# XtendTeensy.net
KiCad netlist of a schematic drawn in EAGLE
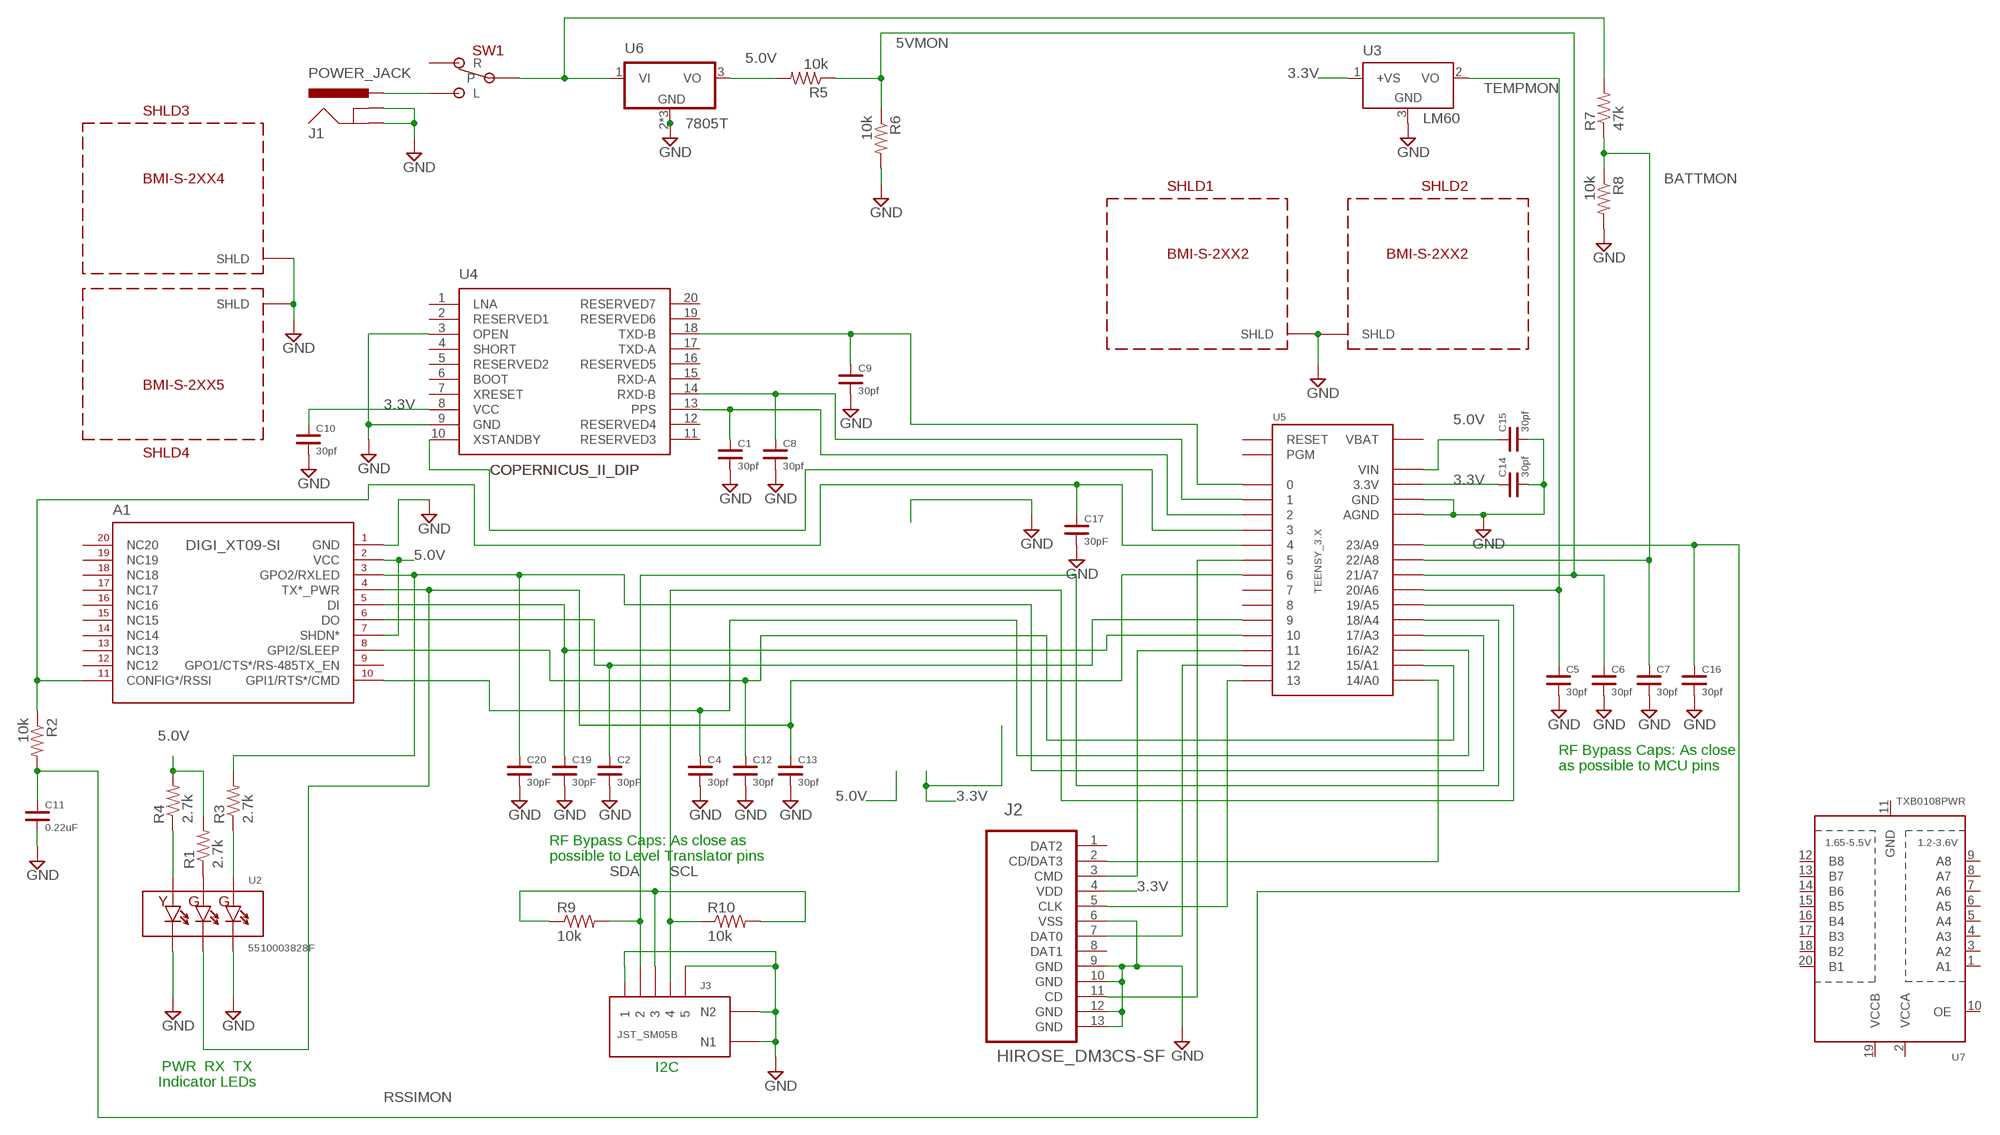
[diagram p0: schematic, sheet 1]

(export (version "E")
  (design (tool "Eeschema 10.0.6"))
  (components
    (comp (ref "A1")
      (value "DIGI_XT09-SI")
      (footprint "eagle-import:DIGI_XT09-SI")
      (libsource (lib "eagle-import") (part "DIGI_XT09-SI"))
    )
    (comp (ref "C1")
      (value "30pf")
      (footprint "eagle-import:C0603")
      (libsource (lib "eagle-import") (part "C-USC0603"))
    )
    (comp (ref "C2")
      (value "30pF")
      (footprint "eagle-import:C0603")
      (libsource (lib "eagle-import") (part "C-USC0603"))
    )
    (comp (ref "C4")
      (value "30pf")
      (footprint "eagle-import:C0603")
      (libsource (lib "eagle-import") (part "C-USC0603"))
    )
    (comp (ref "C5")
      (value "30pf")
      (footprint "eagle-import:C0603")
      (libsource (lib "eagle-import") (part "C-USC0603"))
    )
    (comp (ref "C6")
      (value "30pf")
      (footprint "eagle-import:C0603")
      (libsource (lib "eagle-import") (part "C-USC0603"))
    )
    (comp (ref "C7")
      (value "30pf")
      (footprint "eagle-import:C0603")
      (libsource (lib "eagle-import") (part "C-USC0603"))
    )
    (comp (ref "C8")
      (value "30pf")
      (footprint "eagle-import:C0603")
      (libsource (lib "eagle-import") (part "C-USC0603"))
    )
    (comp (ref "C9")
      (value "30pf")
      (footprint "eagle-import:C0603")
      (libsource (lib "eagle-import") (part "C-USC0603"))
    )
    (comp (ref "C10")
      (value "30pf")
      (footprint "eagle-import:C0603")
      (libsource (lib "eagle-import") (part "C-USC0603"))
    )
    (comp (ref "C11")
      (value "0.22uF")
      (footprint "eagle-import:C0603")
      (libsource (lib "eagle-import") (part "C-USC0603"))
    )
    (comp (ref "C12")
      (value "30pf")
      (footprint "eagle-import:C0603")
      (libsource (lib "eagle-import") (part "C-USC0603"))
    )
    (comp (ref "C13")
      (value "30pf")
      (footprint "eagle-import:C0603")
      (libsource (lib "eagle-import") (part "C-USC0603"))
    )
    (comp (ref "C14")
      (value "30pf")
      (footprint "eagle-import:C0603")
      (libsource (lib "eagle-import") (part "C-USC0603"))
    )
    (comp (ref "C15")
      (value "30pf")
      (footprint "eagle-import:C0603")
      (libsource (lib "eagle-import") (part "C-USC0603"))
    )
    (comp (ref "C16")
      (value "30pf")
      (footprint "eagle-import:C0603")
      (libsource (lib "eagle-import") (part "C-USC0603"))
    )
    (comp (ref "C17")
      (value "30pF")
      (footprint "eagle-import:C0603")
      (libsource (lib "eagle-import") (part "C-USC0603"))
    )
    (comp (ref "C19")
      (value "30pF")
      (footprint "eagle-import:C0603")
      (libsource (lib "eagle-import") (part "C-USC0603"))
    )
    (comp (ref "C20")
      (value "30pF")
      (footprint "eagle-import:C0603")
      (libsource (lib "eagle-import") (part "C-USC0603"))
    )
    (comp (ref "J1")
      (value "POWER_JACK")
      (footprint "eagle-import:PWR_JACK_BB")
      (libsource (lib "eagle-import") (part "POWER_JACK"))
    )
    (comp (ref "J2")
      (value "HIROSE_DM3CS-SF")
      (footprint "eagle-import:HIROSE_DM3CS-SF")
      (fields (field (name "MPN") "DM3CS-SF"))
      (libsource (lib "eagle-import") (part "HIROSE_DM3CS-SF"))
    )
    (comp (ref "J3")
      (value "JST_SM05B")
      (footprint "eagle-import:JST_SM05B")
      (libsource (lib "eagle-import") (part "JST_SM05B"))
    )
    (comp (ref "R1")
      (value "2.7k")
      (footprint "eagle-import:R0805")
      (libsource (lib "eagle-import") (part "R-US_R0805"))
    )
    (comp (ref "R2")
      (value "10k")
      (footprint "eagle-import:R0805")
      (libsource (lib "eagle-import") (part "R-US_R0805"))
    )
    (comp (ref "R3")
      (value "2.7k")
      (footprint "eagle-import:R0805")
      (libsource (lib "eagle-import") (part "R-US_R0805"))
    )
    (comp (ref "R4")
      (value "2.7k")
      (footprint "eagle-import:R0805")
      (libsource (lib "eagle-import") (part "R-US_R0805"))
    )
    (comp (ref "R5")
      (value "10k")
      (footprint "eagle-import:R0805")
      (libsource (lib "eagle-import") (part "R-US_R0805"))
    )
    (comp (ref "R6")
      (value "10k")
      (footprint "eagle-import:R0805")
      (libsource (lib "eagle-import") (part "R-US_R0805"))
    )
    (comp (ref "R7")
      (value "47k")
      (footprint "eagle-import:R0805")
      (libsource (lib "eagle-import") (part "R-US_R0805"))
    )
    (comp (ref "R8")
      (value "10k")
      (footprint "eagle-import:R0805")
      (libsource (lib "eagle-import") (part "R-US_R0805"))
    )
    (comp (ref "R9")
      (value "10k")
      (footprint "eagle-import:R0805")
      (libsource (lib "eagle-import") (part "R-US_R0805"))
    )
    (comp (ref "R10")
      (value "10k")
      (footprint "eagle-import:R0805")
      (libsource (lib "eagle-import") (part "R-US_R0805"))
    )
    (comp (ref "SHLD1")
      (value "BMI-S-2XX2")
      (footprint "eagle-import:BMI-S-207-F")
      (libsource (lib "eagle-import") (part "BMI-S-2XX2"))
    )
    (comp (ref "SHLD2")
      (value "BMI-S-2XX2")
      (footprint "eagle-import:BMI-S-207-F")
      (libsource (lib "eagle-import") (part "BMI-S-2XX2"))
    )
    (comp (ref "SHLD3")
      (value "BMI-S-2XX4")
      (footprint "eagle-import:BMI-S-206-F_COPERNICUS")
      (libsource (lib "eagle-import") (part "BMI-S-2XX4"))
    )
    (comp (ref "SHLD4")
      (value "BMI-S-2XX5")
      (footprint "eagle-import:BMI-S-206-F_COPERNICUS_M")
      (libsource (lib "eagle-import") (part "BMI-S-2XX5"))
    )
    (comp (ref "SW1")
      (value "SPDT_RA_3A")
      (footprint "eagle-import:ESWITCH_SPDT_RA")
      (libsource (lib "eagle-import") (part "SPDT_RA_3A"))
    )
    (comp (ref "U2")
      (value "5510003828F")
      (footprint "eagle-import:TRIPLE_LED_SIDE_0.1IN")
      (libsource (lib "eagle-import") (part "5510003828F"))
    )
    (comp (ref "U3")
      (value "LM60")
      (footprint "eagle-import:TO92")
      (libsource (lib "eagle-import") (part "LM60"))
    )
    (comp (ref "U4")
      (value "COPERNICUS_II_DIP")
      (footprint "eagle-import:COPERNICUS_II_DIP")
      (libsource (lib "eagle-import") (part "COPERNICUS_II_DIP"))
    )
    (comp (ref "U5")
      (value "TEENSY_3.X")
      (footprint "eagle-import:TEENSY_3.X_PERIPHERY")
      (libsource (lib "eagle-import") (part "TEENSY_3.X"))
    )
    (comp (ref "U6")
      (value "7805T")
      (footprint "eagle-import:TO220H")
      (libsource (lib "eagle-import") (part "78T05"))
    )
    (comp (ref "U7")
      (value "TXB0108PWR")
      (footprint "eagle-import:TSSOP20")
      (libsource (lib "eagle-import") (part "TXB0108PWR"))
    )
  )
  (nets
    (net (code "1") (name "/3.3V") (class "Default")
      (node (ref "C10") (pin "1") (pinfunction "1_1") (pintype "passive"))
      (node (ref "C14") (pin "1") (pinfunction "1_1") (pintype "passive"))
      (node (ref "J2") (pin "4") (pinfunction "VDD_4") (pintype "passive"))
      (node (ref "U3") (pin "1") (pinfunction "+VS_1") (pintype "input"))
      (node (ref "U4") (pin "8") (pinfunction "VCC_8") (pintype "bidirectional"))
      (node (ref "U5") (pin "3.3V") (pinfunction "3.3V_3.3V") (pintype "power_in"))
      (node (ref "U5") (pin "3.3V1") (pinfunction "3.3V_3.3V1") (pintype "power_in"))
    )
    (net (code "2") (name "/5.0V") (class "Default")
      (node (ref "A1") (pin "P$2") (pinfunction "VCC_P$2") (pintype "power_in"))
      (node (ref "A1") (pin "P$7") (pinfunction "SHDN*_P$7") (pintype "input"))
      (node (ref "C15") (pin "1") (pinfunction "1_1") (pintype "passive"))
      (node (ref "R1") (pin "2") (pinfunction "2_2") (pintype "passive"))
      (node (ref "R4") (pin "2") (pinfunction "2_2") (pintype "passive"))
      (node (ref "R5") (pin "2") (pinfunction "2_2") (pintype "passive"))
      (node (ref "U5") (pin "VIN") (pinfunction "VIN_VIN") (pintype "input"))
      (node (ref "U6") (pin "3") (pinfunction "VO_3") (pintype "passive"))
    )
    (net (code "3") (name "/5VMON") (class "Default")
      (node (ref "C6") (pin "1") (pinfunction "1_1") (pintype "passive"))
      (node (ref "R5") (pin "1") (pinfunction "1_1") (pintype "passive"))
      (node (ref "R6") (pin "1") (pinfunction "1_1") (pintype "passive"))
      (node (ref "U5") (pin "21/A7") (pinfunction "21/A7_21/A7") (pintype "bidirectional"))
    )
    (net (code "4") (name "/BATTMON") (class "Default")
      (node (ref "C7") (pin "1") (pinfunction "1_1") (pintype "passive"))
      (node (ref "R7") (pin "1") (pinfunction "1_1") (pintype "passive"))
      (node (ref "R8") (pin "1") (pinfunction "1_1") (pintype "passive"))
      (node (ref "U5") (pin "22/A8") (pinfunction "22/A8_22/A8") (pintype "bidirectional"))
    )
    (net (code "5") (name "/RSSIMON") (class "Default")
      (node (ref "C11") (pin "1") (pinfunction "1_1") (pintype "passive"))
      (node (ref "C16") (pin "1") (pinfunction "1_1") (pintype "passive"))
      (node (ref "R2") (pin "2") (pinfunction "2_2") (pintype "passive"))
      (node (ref "U5") (pin "23/A9") (pinfunction "23/A9_23/A9") (pintype "bidirectional"))
    )
    (net (code "6") (name "/SCL") (class "Default")
      (node (ref "J3") (pin "P$4") (pinfunction "4_P$4") (pintype "bidirectional"))
      (node (ref "R10") (pin "1") (pinfunction "1_1") (pintype "passive"))
      (node (ref "U5") (pin "19/A5") (pinfunction "19/A5_19/A5") (pintype "bidirectional"))
    )
    (net (code "7") (name "/SDA") (class "Default")
      (node (ref "J3") (pin "P$2") (pinfunction "2_P$2") (pintype "bidirectional"))
      (node (ref "R9") (pin "2") (pinfunction "2_2") (pintype "passive"))
      (node (ref "U5") (pin "18/A4") (pinfunction "18/A4_18/A4") (pintype "bidirectional"))
    )
    (net (code "8") (name "/TEMPMON") (class "Default")
      (node (ref "C5") (pin "1") (pinfunction "1_1") (pintype "passive"))
      (node (ref "U3") (pin "2") (pinfunction "VO_2") (pintype "input"))
      (node (ref "U5") (pin "20/A6") (pinfunction "20/A6_20/A6") (pintype "bidirectional"))
    )
    (net (code "9") (name "GND") (class "Default")
      (node (ref "A1") (pin "P$1") (pinfunction "GND_P$1") (pintype "power_in"))
      (node (ref "A1") (pin "P$21") (pinfunction "GND_P$21") (pintype "power_in"))
      (node (ref "A1") (pin "P$22") (pinfunction "GND_P$22") (pintype "power_in"))
      (node (ref "A1") (pin "P$23") (pinfunction "GND_P$23") (pintype "power_in"))
      (node (ref "A1") (pin "P$24") (pinfunction "GND_P$24") (pintype "power_in"))
      (node (ref "C1") (pin "2") (pinfunction "2_2") (pintype "passive"))
      (node (ref "C10") (pin "2") (pinfunction "2_2") (pintype "passive"))
      (node (ref "C11") (pin "2") (pinfunction "2_2") (pintype "passive"))
      (node (ref "C12") (pin "2") (pinfunction "2_2") (pintype "passive"))
      (node (ref "C13") (pin "2") (pinfunction "2_2") (pintype "passive"))
      (node (ref "C14") (pin "2") (pinfunction "2_2") (pintype "passive"))
      (node (ref "C15") (pin "2") (pinfunction "2_2") (pintype "passive"))
      (node (ref "C16") (pin "2") (pinfunction "2_2") (pintype "passive"))
      (node (ref "C17") (pin "2") (pinfunction "2_2") (pintype "passive"))
      (node (ref "C19") (pin "2") (pinfunction "2_2") (pintype "passive"))
      (node (ref "C2") (pin "2") (pinfunction "2_2") (pintype "passive"))
      (node (ref "C20") (pin "2") (pinfunction "2_2") (pintype "passive"))
      (node (ref "C4") (pin "2") (pinfunction "2_2") (pintype "passive"))
      (node (ref "C5") (pin "2") (pinfunction "2_2") (pintype "passive"))
      (node (ref "C6") (pin "2") (pinfunction "2_2") (pintype "passive"))
      (node (ref "C7") (pin "2") (pinfunction "2_2") (pintype "passive"))
      (node (ref "C8") (pin "2") (pinfunction "2_2") (pintype "passive"))
      (node (ref "C9") (pin "2") (pinfunction "2_2") (pintype "passive"))
      (node (ref "J1") (pin "GND") (pinfunction "GND_GND") (pintype "bidirectional"))
      (node (ref "J1") (pin "GNDBREAK") (pinfunction "GNDBREAK_GNDBREAK") (pintype "bidirectional"))
      (node (ref "J2") (pin "10") (pinfunction "GND_10") (pintype "passive"))
      (node (ref "J2") (pin "12") (pinfunction "GND_12") (pintype "passive"))
      (node (ref "J2") (pin "13") (pinfunction "GND_13") (pintype "passive"))
      (node (ref "J2") (pin "6") (pinfunction "VSS_6") (pintype "passive"))
      (node (ref "J2") (pin "9") (pinfunction "GND_9") (pintype "passive"))
      (node (ref "J3") (pin "P$1") (pinfunction "1_P$1") (pintype "bidirectional"))
      (node (ref "J3") (pin "P$5") (pinfunction "5_P$5") (pintype "bidirectional"))
      (node (ref "J3") (pin "P$6") (pinfunction "N1_P$6") (pintype "bidirectional"))
      (node (ref "J3") (pin "P$7") (pinfunction "N2_P$7") (pintype "bidirectional"))
      (node (ref "R6") (pin "2") (pinfunction "2_2") (pintype "passive"))
      (node (ref "R8") (pin "2") (pinfunction "2_2") (pintype "passive"))
      (node (ref "SHLD1") (pin "P$10") (pinfunction "SHLD_P$10") (pintype "bidirectional"))
      (node (ref "SHLD1") (pin "P$11") (pinfunction "SHLD_P$11") (pintype "bidirectional"))
      (node (ref "SHLD1") (pin "P$12") (pinfunction "SHLD_P$12") (pintype "bidirectional"))
      (node (ref "SHLD1") (pin "P$14") (pinfunction "SHLD_P$14") (pintype "bidirectional"))
      (node (ref "SHLD1") (pin "P$15") (pinfunction "SHLD_P$15") (pintype "bidirectional"))
      (node (ref "SHLD1") (pin "P$16") (pinfunction "SHLD_P$16") (pintype "bidirectional"))
      (node (ref "SHLD1") (pin "P$17") (pinfunction "SHLD_P$17") (pintype "bidirectional"))
      (node (ref "SHLD1") (pin "P$18") (pinfunction "SHLD_P$18") (pintype "bidirectional"))
      (node (ref "SHLD1") (pin "P$19") (pinfunction "SHLD_P$19") (pintype "bidirectional"))
      (node (ref "SHLD1") (pin "P$2") (pinfunction "SHLD_P$2") (pintype "bidirectional"))
      (node (ref "SHLD1") (pin "P$20") (pinfunction "SHLD_P$20") (pintype "bidirectional"))
      (node (ref "SHLD1") (pin "P$21") (pinfunction "SHLD_P$21") (pintype "bidirectional"))
      (node (ref "SHLD1") (pin "P$22") (pinfunction "SHLD_P$22") (pintype "bidirectional"))
      (node (ref "SHLD1") (pin "P$23") (pinfunction "SHLD_P$23") (pintype "bidirectional"))
      (node (ref "SHLD1") (pin "P$24") (pinfunction "SHLD_P$24") (pintype "bidirectional"))
      (node (ref "SHLD1") (pin "P$25") (pinfunction "SHLD_P$25") (pintype "bidirectional"))
      (node (ref "SHLD1") (pin "P$26") (pinfunction "SHLD_P$26") (pintype "bidirectional"))
      (node (ref "SHLD1") (pin "P$27") (pinfunction "SHLD_P$27") (pintype "bidirectional"))
      (node (ref "SHLD1") (pin "P$28") (pinfunction "SHLD_P$28") (pintype "bidirectional"))
      (node (ref "SHLD1") (pin "P$29") (pinfunction "SHLD_P$29") (pintype "bidirectional"))
      (node (ref "SHLD1") (pin "P$3") (pinfunction "SHLD_P$3") (pintype "bidirectional"))
      (node (ref "SHLD1") (pin "P$30") (pinfunction "SHLD_P$30") (pintype "bidirectional"))
      (node (ref "SHLD1") (pin "P$31") (pinfunction "SHLD_P$31") (pintype "bidirectional"))
      (node (ref "SHLD1") (pin "P$32") (pinfunction "SHLD_P$32") (pintype "bidirectional"))
      (node (ref "SHLD1") (pin "P$33") (pinfunction "SHLD_P$33") (pintype "bidirectional"))
      (node (ref "SHLD1") (pin "P$34") (pinfunction "SHLD_P$34") (pintype "bidirectional"))
      (node (ref "SHLD1") (pin "P$4") (pinfunction "SHLD_P$4") (pintype "bidirectional"))
      (node (ref "SHLD1") (pin "P$5") (pinfunction "SHLD_P$5") (pintype "bidirectional"))
      (node (ref "SHLD1") (pin "P$6") (pinfunction "SHLD_P$6") (pintype "bidirectional"))
      (node (ref "SHLD1") (pin "P$7") (pinfunction "SHLD_P$7") (pintype "bidirectional"))
      (node (ref "SHLD1") (pin "P$8") (pinfunction "SHLD_P$8") (pintype "bidirectional"))
      (node (ref "SHLD1") (pin "P$9") (pinfunction "SHLD_P$9") (pintype "bidirectional"))
      (node (ref "SHLD2") (pin "P$10") (pinfunction "SHLD_P$10") (pintype "bidirectional"))
      (node (ref "SHLD2") (pin "P$11") (pinfunction "SHLD_P$11") (pintype "bidirectional"))
      (node (ref "SHLD2") (pin "P$12") (pinfunction "SHLD_P$12") (pintype "bidirectional"))
      (node (ref "SHLD2") (pin "P$14") (pinfunction "SHLD_P$14") (pintype "bidirectional"))
      (node (ref "SHLD2") (pin "P$15") (pinfunction "SHLD_P$15") (pintype "bidirectional"))
      (node (ref "SHLD2") (pin "P$16") (pinfunction "SHLD_P$16") (pintype "bidirectional"))
      (node (ref "SHLD2") (pin "P$17") (pinfunction "SHLD_P$17") (pintype "bidirectional"))
      (node (ref "SHLD2") (pin "P$18") (pinfunction "SHLD_P$18") (pintype "bidirectional"))
      (node (ref "SHLD2") (pin "P$19") (pinfunction "SHLD_P$19") (pintype "bidirectional"))
      (node (ref "SHLD2") (pin "P$2") (pinfunction "SHLD_P$2") (pintype "bidirectional"))
      (node (ref "SHLD2") (pin "P$20") (pinfunction "SHLD_P$20") (pintype "bidirectional"))
      (node (ref "SHLD2") (pin "P$21") (pinfunction "SHLD_P$21") (pintype "bidirectional"))
      (node (ref "SHLD2") (pin "P$22") (pinfunction "SHLD_P$22") (pintype "bidirectional"))
      (node (ref "SHLD2") (pin "P$23") (pinfunction "SHLD_P$23") (pintype "bidirectional"))
      (node (ref "SHLD2") (pin "P$24") (pinfunction "SHLD_P$24") (pintype "bidirectional"))
      (node (ref "SHLD2") (pin "P$25") (pinfunction "SHLD_P$25") (pintype "bidirectional"))
      (node (ref "SHLD2") (pin "P$26") (pinfunction "SHLD_P$26") (pintype "bidirectional"))
      (node (ref "SHLD2") (pin "P$27") (pinfunction "SHLD_P$27") (pintype "bidirectional"))
      (node (ref "SHLD2") (pin "P$28") (pinfunction "SHLD_P$28") (pintype "bidirectional"))
      (node (ref "SHLD2") (pin "P$29") (pinfunction "SHLD_P$29") (pintype "bidirectional"))
      (node (ref "SHLD2") (pin "P$3") (pinfunction "SHLD_P$3") (pintype "bidirectional"))
      (node (ref "SHLD2") (pin "P$30") (pinfunction "SHLD_P$30") (pintype "bidirectional"))
      (node (ref "SHLD2") (pin "P$31") (pinfunction "SHLD_P$31") (pintype "bidirectional"))
      (node (ref "SHLD2") (pin "P$32") (pinfunction "SHLD_P$32") (pintype "bidirectional"))
      (node (ref "SHLD2") (pin "P$33") (pinfunction "SHLD_P$33") (pintype "bidirectional"))
      (node (ref "SHLD2") (pin "P$34") (pinfunction "SHLD_P$34") (pintype "bidirectional"))
      (node (ref "SHLD2") (pin "P$4") (pinfunction "SHLD_P$4") (pintype "bidirectional"))
      (node (ref "SHLD2") (pin "P$5") (pinfunction "SHLD_P$5") (pintype "bidirectional"))
      (node (ref "SHLD2") (pin "P$6") (pinfunction "SHLD_P$6") (pintype "bidirectional"))
      (node (ref "SHLD2") (pin "P$7") (pinfunction "SHLD_P$7") (pintype "bidirectional"))
      (node (ref "SHLD2") (pin "P$8") (pinfunction "SHLD_P$8") (pintype "bidirectional"))
      (node (ref "SHLD2") (pin "P$9") (pinfunction "SHLD_P$9") (pintype "bidirectional"))
      (node (ref "SHLD3") (pin "P$10") (pinfunction "SHLD_P$10") (pintype "bidirectional"))
      (node (ref "SHLD3") (pin "P$11") (pinfunction "SHLD_P$11") (pintype "bidirectional"))
      (node (ref "SHLD3") (pin "P$12") (pinfunction "SHLD_P$12") (pintype "bidirectional"))
      (node (ref "SHLD3") (pin "P$14") (pinfunction "SHLD_P$14") (pintype "bidirectional"))
      (node (ref "SHLD3") (pin "P$15") (pinfunction "SHLD_P$15") (pintype "bidirectional"))
      (node (ref "SHLD3") (pin "P$16") (pinfunction "SHLD_P$16") (pintype "bidirectional"))
      (node (ref "SHLD3") (pin "P$17") (pinfunction "SHLD_P$17") (pintype "bidirectional"))
      (node (ref "SHLD3") (pin "P$18") (pinfunction "SHLD_P$18") (pintype "bidirectional"))
      (node (ref "SHLD3") (pin "P$2") (pinfunction "SHLD_P$2") (pintype "bidirectional"))
      (node (ref "SHLD3") (pin "P$21") (pinfunction "SHLD_P$21") (pintype "bidirectional"))
      (node (ref "SHLD3") (pin "P$22") (pinfunction "SHLD_P$22") (pintype "bidirectional"))
      (node (ref "SHLD3") (pin "P$23") (pinfunction "SHLD_P$23") (pintype "bidirectional"))
      (node (ref "SHLD3") (pin "P$24") (pinfunction "SHLD_P$24") (pintype "bidirectional"))
      (node (ref "SHLD3") (pin "P$25") (pinfunction "SHLD_P$25") (pintype "bidirectional"))
      (node (ref "SHLD3") (pin "P$3") (pinfunction "SHLD_P$3") (pintype "bidirectional"))
      (node (ref "SHLD3") (pin "P$31") (pinfunction "SHLD_P$31") (pintype "bidirectional"))
      (node (ref "SHLD3") (pin "P$32") (pinfunction "SHLD_P$32") (pintype "bidirectional"))
      (node (ref "SHLD3") (pin "P$4") (pinfunction "SHLD_P$4") (pintype "bidirectional"))
      (node (ref "SHLD3") (pin "P$5") (pinfunction "SHLD_P$5") (pintype "bidirectional"))
      (node (ref "SHLD3") (pin "P$6") (pinfunction "SHLD_P$6") (pintype "bidirectional"))
      (node (ref "SHLD3") (pin "P$7") (pinfunction "SHLD_P$7") (pintype "bidirectional"))
      (node (ref "SHLD3") (pin "P$8") (pinfunction "SHLD_P$8") (pintype "bidirectional"))
      (node (ref "SHLD4") (pin "P$1") (pinfunction "SHLD_P$1") (pintype "bidirectional"))
      (node (ref "SHLD4") (pin "P$12") (pinfunction "SHLD_P$12") (pintype "bidirectional"))
      (node (ref "SHLD4") (pin "P$14") (pinfunction "SHLD_P$14") (pintype "bidirectional"))
      (node (ref "SHLD4") (pin "P$15") (pinfunction "SHLD_P$15") (pintype "bidirectional"))
      (node (ref "SHLD4") (pin "P$16") (pinfunction "SHLD_P$16") (pintype "bidirectional"))
      (node (ref "SHLD4") (pin "P$17") (pinfunction "SHLD_P$17") (pintype "bidirectional"))
      (node (ref "SHLD4") (pin "P$18") (pinfunction "SHLD_P$18") (pintype "bidirectional"))
      (node (ref "SHLD4") (pin "P$2") (pinfunction "SHLD_P$2") (pintype "bidirectional"))
      (node (ref "SHLD4") (pin "P$21") (pinfunction "SHLD_P$21") (pintype "bidirectional"))
      (node (ref "SHLD4") (pin "P$22") (pinfunction "SHLD_P$22") (pintype "bidirectional"))
      (node (ref "SHLD4") (pin "P$23") (pinfunction "SHLD_P$23") (pintype "bidirectional"))
      (node (ref "SHLD4") (pin "P$24") (pinfunction "SHLD_P$24") (pintype "bidirectional"))
      (node (ref "SHLD4") (pin "P$25") (pinfunction "SHLD_P$25") (pintype "bidirectional"))
      (node (ref "SHLD4") (pin "P$3") (pinfunction "SHLD_P$3") (pintype "bidirectional"))
      (node (ref "SHLD4") (pin "P$31") (pinfunction "SHLD_P$31") (pintype "bidirectional"))
      (node (ref "SHLD4") (pin "P$32") (pinfunction "SHLD_P$32") (pintype "bidirectional"))
      (node (ref "SHLD4") (pin "P$4") (pinfunction "SHLD_P$4") (pintype "bidirectional"))
      (node (ref "SHLD4") (pin "P$5") (pinfunction "SHLD_P$5") (pintype "bidirectional"))
      (node (ref "SHLD4") (pin "P$6") (pinfunction "SHLD_P$6") (pintype "bidirectional"))
      (node (ref "SHLD4") (pin "P$7") (pinfunction "SHLD_P$7") (pintype "bidirectional"))
      (node (ref "SHLD4") (pin "P$8") (pinfunction "SHLD_P$8") (pintype "bidirectional"))
      (node (ref "SHLD4") (pin "P$9") (pinfunction "SHLD_P$9") (pintype "bidirectional"))
      (node (ref "U2") (pin "P$1") (pinfunction "1_P$1") (pintype "bidirectional"))
      (node (ref "U2") (pin "P$5") (pinfunction "5_P$5") (pintype "bidirectional"))
      (node (ref "U3") (pin "3") (pinfunction "GND_3") (pintype "power_in"))
      (node (ref "U4") (pin "3") (pinfunction "OPEN_3") (pintype "bidirectional"))
      (node (ref "U4") (pin "9") (pinfunction "GND_9") (pintype "bidirectional"))
      (node (ref "U5") (pin "AGND") (pinfunction "AGND_AGND") (pintype "power_in"))
      (node (ref "U5") (pin "GND") (pinfunction "GND_GND") (pintype "power_in"))
      (node (ref "U5") (pin "GND1") (pinfunction "GND_GND1") (pintype "power_in"))
      (node (ref "U6") (pin "2") (pinfunction "GND_2") (pintype "passive"))
      (node (ref "U6") (pin "MOUNT") (pinfunction "GND_MOUNT") (pintype "passive"))
      (node (ref "U6") (pin "TAB") (pinfunction "GND_TAB") (pintype "passive"))
    )
    (net (code "10") (name "Net-(A1-CONFIG*{slash}RSSI)") (class "Default")
      (node (ref "A1") (pin "P$11") (pinfunction "CONFIG*/RSSI_P$11") (pintype "bidirectional"))
      (node (ref "C17") (pin "1") (pinfunction "1_1") (pintype "passive"))
      (node (ref "R2") (pin "1") (pinfunction "1_1") (pintype "passive"))
      (node (ref "U5") (pin "4") (pinfunction "4_4") (pintype "bidirectional"))
    )
    (net (code "11") (name "Net-(A1-DI)") (class "Default")
      (node (ref "A1") (pin "P$5") (pinfunction "DI_P$5") (pintype "bidirectional"))
      (node (ref "C19") (pin "1") (pinfunction "1_1") (pintype "passive"))
      (node (ref "U5") (pin "10") (pinfunction "10_10") (pintype "bidirectional"))
    )
    (net (code "12") (name "Net-(A1-DO)") (class "Default")
      (node (ref "A1") (pin "P$6") (pinfunction "DO_P$6") (pintype "output"))
      (node (ref "C2") (pin "1") (pinfunction "1_1") (pintype "passive"))
      (node (ref "U5") (pin "9") (pinfunction "9_9") (pintype "bidirectional"))
    )
    (net (code "13") (name "Net-(A1-GPI1{slash}RTS*{slash}CMD)") (class "Default")
      (node (ref "A1") (pin "P$10") (pinfunction "GPI1/RTS*/CMD_P$10") (pintype "input"))
      (node (ref "C4") (pin "1") (pinfunction "1_1") (pintype "passive"))
      (node (ref "U5") (pin "16/A2") (pinfunction "16/A2_16/A2") (pintype "bidirectional"))
    )
    (net (code "14") (name "Net-(A1-GPI2{slash}SLEEP)") (class "Default")
      (node (ref "A1") (pin "P$8") (pinfunction "GPI2/SLEEP_P$8") (pintype "input"))
      (node (ref "C12") (pin "1") (pinfunction "1_1") (pintype "passive"))
      (node (ref "U5") (pin "15/A1") (pinfunction "15/A1_15/A1") (pintype "bidirectional"))
    )
    (net (code "15") (name "Net-(A1-GPO2{slash}RXLED)") (class "Default")
      (node (ref "A1") (pin "P$3") (pinfunction "GPO2/RXLED_P$3") (pintype "input"))
      (node (ref "C20") (pin "1") (pinfunction "1_1") (pintype "passive"))
      (node (ref "R3") (pin "2") (pinfunction "2_2") (pintype "passive"))
      (node (ref "U5") (pin "17/A3") (pinfunction "17/A3_17/A3") (pintype "bidirectional"))
    )
    (net (code "16") (name "Net-(A1-TX*_PWR)") (class "Default")
      (node (ref "A1") (pin "P$4") (pinfunction "TX*_PWR_P$4") (pintype "output"))
      (node (ref "C13") (pin "1") (pinfunction "1_1") (pintype "passive"))
      (node (ref "U2") (pin "P$3") (pinfunction "3_P$3") (pintype "bidirectional"))
      (node (ref "U5") (pin "6") (pinfunction "6_6") (pintype "bidirectional"))
    )
    (net (code "17") (name "Net-(J2-CD)") (class "Default")
      (node (ref "J2") (pin "11") (pinfunction "CD_11") (pintype "passive"))
      (node (ref "U5") (pin "5") (pinfunction "5_5") (pintype "bidirectional"))
    )
    (net (code "18") (name "Net-(J2-CD{slash}DAT3)") (class "Default")
      (node (ref "J2") (pin "2") (pinfunction "CD/DAT3_2") (pintype "passive"))
      (node (ref "U5") (pin "14/A0") (pinfunction "14/A0_14/A0") (pintype "bidirectional"))
    )
    (net (code "19") (name "Net-(J2-CLK)") (class "Default")
      (node (ref "J2") (pin "5") (pinfunction "CLK_5") (pintype "passive"))
      (node (ref "U5") (pin "13") (pinfunction "13_13") (pintype "bidirectional"))
    )
    (net (code "20") (name "Net-(J2-CMD)") (class "Default")
      (node (ref "J2") (pin "3") (pinfunction "CMD_3") (pintype "passive"))
      (node (ref "U5") (pin "11") (pinfunction "11_11") (pintype "bidirectional"))
    )
    (net (code "21") (name "Net-(J2-DAT0)") (class "Default")
      (node (ref "J2") (pin "7") (pinfunction "DAT0_7") (pintype "passive"))
      (node (ref "U5") (pin "12") (pinfunction "12_12") (pintype "bidirectional"))
    )
    (net (code "22") (name "Net-(J3-3)") (class "Default")
      (node (ref "J3") (pin "P$3") (pinfunction "3_P$3") (pintype "bidirectional"))
      (node (ref "R10") (pin "2") (pinfunction "2_2") (pintype "passive"))
      (node (ref "R9") (pin "1") (pinfunction "1_1") (pintype "passive"))
    )
    (net (code "23") (name "Net-(SW1-L)") (class "Default")
      (node (ref "J1") (pin "PWR") (pinfunction "PWR_PWR") (pintype "bidirectional"))
      (node (ref "SW1") (pin "P$1") (pinfunction "L_P$1") (pintype "bidirectional"))
    )
    (net (code "24") (name "Net-(SW1-P)") (class "Default")
      (node (ref "R7") (pin "2") (pinfunction "2_2") (pintype "passive"))
      (node (ref "SW1") (pin "P$2") (pinfunction "P_P$2") (pintype "bidirectional"))
      (node (ref "U6") (pin "1") (pinfunction "VI_1") (pintype "input"))
    )
    (net (code "25") (name "Net-(U2-2)") (class "Default")
      (node (ref "R3") (pin "1") (pinfunction "1_1") (pintype "passive"))
      (node (ref "U2") (pin "P$2") (pinfunction "2_P$2") (pintype "bidirectional"))
    )
    (net (code "26") (name "Net-(U2-4)") (class "Default")
      (node (ref "R1") (pin "1") (pinfunction "1_1") (pintype "passive"))
      (node (ref "U2") (pin "P$4") (pinfunction "4_P$4") (pintype "bidirectional"))
    )
    (net (code "27") (name "Net-(U2-6)") (class "Default")
      (node (ref "R4") (pin "1") (pinfunction "1_1") (pintype "passive"))
      (node (ref "U2") (pin "P$6") (pinfunction "6_P$6") (pintype "bidirectional"))
    )
    (net (code "28") (name "Net-(U4-PPS)") (class "Default")
      (node (ref "C1") (pin "1") (pinfunction "1_1") (pintype "passive"))
      (node (ref "U4") (pin "13") (pinfunction "PPS_13") (pintype "bidirectional"))
      (node (ref "U5") (pin "2") (pinfunction "2_2") (pintype "bidirectional"))
    )
    (net (code "29") (name "Net-(U4-RXD-B)") (class "Default")
      (node (ref "C8") (pin "1") (pinfunction "1_1") (pintype "passive"))
      (node (ref "U4") (pin "14") (pinfunction "RXD-B_14") (pintype "bidirectional"))
      (node (ref "U5") (pin "1") (pinfunction "1_1") (pintype "bidirectional"))
    )
    (net (code "30") (name "Net-(U4-TXD-B)") (class "Default")
      (node (ref "C9") (pin "1") (pinfunction "1_1") (pintype "passive"))
      (node (ref "U4") (pin "18") (pinfunction "TXD-B_18") (pintype "bidirectional"))
      (node (ref "U5") (pin "0") (pinfunction "0_0") (pintype "bidirectional"))
    )
    (net (code "31") (name "Net-(U4-XSTANDBY)") (class "Default")
      (node (ref "U4") (pin "10") (pinfunction "XSTANDBY_10") (pintype "bidirectional"))
      (node (ref "U5") (pin "3") (pinfunction "3_3") (pintype "bidirectional"))
    )
    (net (code "32") (name "unconnected-(A1-GPO1{slash}CTS*{slash}RS-485TX_EN-PadP$9)") (class "Default")
      (node (ref "A1") (pin "P$9") (pinfunction "GPO1/CTS*/RS-485TX_EN_P$9") (pintype "output"))
    )
    (net (code "33") (name "unconnected-(A1-NC12-PadP$12)") (class "Default")
      (node (ref "A1") (pin "P$12") (pinfunction "NC12_P$12") (pintype "no_connect"))
    )
    (net (code "34") (name "unconnected-(A1-NC13-PadP$13)") (class "Default")
      (node (ref "A1") (pin "P$13") (pinfunction "NC13_P$13") (pintype "no_connect"))
    )
    (net (code "35") (name "unconnected-(A1-NC14-PadP$14)") (class "Default")
      (node (ref "A1") (pin "P$14") (pinfunction "NC14_P$14") (pintype "no_connect"))
    )
    (net (code "36") (name "unconnected-(A1-NC15-PadP$15)") (class "Default")
      (node (ref "A1") (pin "P$15") (pinfunction "NC15_P$15") (pintype "no_connect"))
    )
    (net (code "37") (name "unconnected-(A1-NC16-PadP$16)") (class "Default")
      (node (ref "A1") (pin "P$16") (pinfunction "NC16_P$16") (pintype "no_connect"))
    )
    (net (code "38") (name "unconnected-(A1-NC17-PadP$17)") (class "Default")
      (node (ref "A1") (pin "P$17") (pinfunction "NC17_P$17") (pintype "no_connect"))
    )
    (net (code "39") (name "unconnected-(A1-NC18-PadP$18)") (class "Default")
      (node (ref "A1") (pin "P$18") (pinfunction "NC18_P$18") (pintype "no_connect"))
    )
    (net (code "40") (name "unconnected-(A1-NC19-PadP$19)") (class "Default")
      (node (ref "A1") (pin "P$19") (pinfunction "NC19_P$19") (pintype "no_connect"))
    )
    (net (code "41") (name "unconnected-(A1-NC20-PadP$20)") (class "Default")
      (node (ref "A1") (pin "P$20") (pinfunction "NC20_P$20") (pintype "no_connect"))
    )
    (net (code "42") (name "unconnected-(J2-DAT1-Pad8)") (class "Default")
      (node (ref "J2") (pin "8") (pinfunction "DAT1_8") (pintype "passive"))
    )
    (net (code "43") (name "unconnected-(J2-DAT2-Pad1)") (class "Default")
      (node (ref "J2") (pin "1") (pinfunction "DAT2_1") (pintype "passive"))
    )
    (net (code "44") (name "unconnected-(SW1-R-PadP$3)") (class "Default")
      (node (ref "SW1") (pin "P$3") (pinfunction "R_P$3") (pintype "bidirectional"))
    )
    (net (code "45") (name "unconnected-(U4-BOOT-Pad6)") (class "Default")
      (node (ref "U4") (pin "6") (pinfunction "BOOT_6") (pintype "bidirectional"))
    )
    (net (code "46") (name "unconnected-(U4-LNA-Pad1)") (class "Default")
      (node (ref "U4") (pin "1") (pinfunction "LNA_1") (pintype "bidirectional"))
    )
    (net (code "47") (name "unconnected-(U4-RESERVED1-Pad2)") (class "Default")
      (node (ref "U4") (pin "2") (pinfunction "RESERVED1_2") (pintype "bidirectional"))
    )
    (net (code "48") (name "unconnected-(U4-RESERVED2-Pad5)") (class "Default")
      (node (ref "U4") (pin "5") (pinfunction "RESERVED2_5") (pintype "bidirectional"))
    )
    (net (code "49") (name "unconnected-(U4-RESERVED3-Pad11)") (class "Default")
      (node (ref "U4") (pin "11") (pinfunction "RESERVED3_11") (pintype "bidirectional"))
    )
    (net (code "50") (name "unconnected-(U4-RESERVED4-Pad12)") (class "Default")
      (node (ref "U4") (pin "12") (pinfunction "RESERVED4_12") (pintype "bidirectional"))
    )
    (net (code "51") (name "unconnected-(U4-RESERVED5-Pad16)") (class "Default")
      (node (ref "U4") (pin "16") (pinfunction "RESERVED5_16") (pintype "bidirectional"))
    )
    (net (code "52") (name "unconnected-(U4-RESERVED6-Pad19)") (class "Default")
      (node (ref "U4") (pin "19") (pinfunction "RESERVED6_19") (pintype "bidirectional"))
    )
    (net (code "53") (name "unconnected-(U4-RESERVED7-Pad20)") (class "Default")
      (node (ref "U4") (pin "20") (pinfunction "RESERVED7_20") (pintype "bidirectional"))
    )
    (net (code "54") (name "unconnected-(U4-RXD-A-Pad15)") (class "Default")
      (node (ref "U4") (pin "15") (pinfunction "RXD-A_15") (pintype "bidirectional"))
    )
    (net (code "55") (name "unconnected-(U4-SHORT-Pad4)") (class "Default")
      (node (ref "U4") (pin "4") (pinfunction "SHORT_4") (pintype "bidirectional"))
    )
    (net (code "56") (name "unconnected-(U4-TXD-A-Pad17)") (class "Default")
      (node (ref "U4") (pin "17") (pinfunction "TXD-A_17") (pintype "bidirectional"))
    )
    (net (code "57") (name "unconnected-(U4-XRESET-Pad7)") (class "Default")
      (node (ref "U4") (pin "7") (pinfunction "XRESET_7") (pintype "bidirectional"))
    )
    (net (code "58") (name "unconnected-(U5-Pad7)") (class "Default")
      (node (ref "U5") (pin "7") (pinfunction "7_7") (pintype "bidirectional"))
    )
    (net (code "59") (name "unconnected-(U5-Pad8)") (class "Default")
      (node (ref "U5") (pin "8") (pinfunction "8_8") (pintype "bidirectional"))
    )
    (net (code "60") (name "unconnected-(U5-PadPGM)") (class "Default")
      (node (ref "U5") (pin "PGM") (pinfunction "PGM_PGM") (pintype "bidirectional"))
    )
    (net (code "61") (name "unconnected-(U5-PadVBAT)") (class "Default")
      (node (ref "U5") (pin "VBAT") (pinfunction "VBAT_VBAT") (pintype "no_connect"))
    )
    (net (code "62") (name "unconnected-(U5-RESET-PadRESET{slash}A14{slash}DAC)") (class "Default")
      (node (ref "U5") (pin "RESET/A14/DAC") (pinfunction "RESET_RESET/A14/DAC") (pintype "bidirectional"))
    )
    (net (code "63") (name "unconnected-(U7-A1-Pad1)") (class "Default")
      (node (ref "U7") (pin "1") (pinfunction "A1_1") (pintype "bidirectional"))
    )
    (net (code "64") (name "unconnected-(U7-A2-Pad3)") (class "Default")
      (node (ref "U7") (pin "3") (pinfunction "A2_3") (pintype "bidirectional"))
    )
    (net (code "65") (name "unconnected-(U7-A3-Pad4)") (class "Default")
      (node (ref "U7") (pin "4") (pinfunction "A3_4") (pintype "bidirectional"))
    )
    (net (code "66") (name "unconnected-(U7-A4-Pad5)") (class "Default")
      (node (ref "U7") (pin "5") (pinfunction "A4_5") (pintype "bidirectional"))
    )
    (net (code "67") (name "unconnected-(U7-A5-Pad6)") (class "Default")
      (node (ref "U7") (pin "6") (pinfunction "A5_6") (pintype "bidirectional"))
    )
    (net (code "68") (name "unconnected-(U7-A6-Pad7)") (class "Default")
      (node (ref "U7") (pin "7") (pinfunction "A6_7") (pintype "bidirectional"))
    )
    (net (code "69") (name "unconnected-(U7-A7-Pad8)") (class "Default")
      (node (ref "U7") (pin "8") (pinfunction "A7_8") (pintype "bidirectional"))
    )
    (net (code "70") (name "unconnected-(U7-A8-Pad9)") (class "Default")
      (node (ref "U7") (pin "9") (pinfunction "A8_9") (pintype "bidirectional"))
    )
    (net (code "71") (name "unconnected-(U7-B1-Pad20)") (class "Default")
      (node (ref "U7") (pin "20") (pinfunction "B1_20") (pintype "bidirectional"))
    )
    (net (code "72") (name "unconnected-(U7-B2-Pad18)") (class "Default")
      (node (ref "U7") (pin "18") (pinfunction "B2_18") (pintype "bidirectional"))
    )
    (net (code "73") (name "unconnected-(U7-B3-Pad17)") (class "Default")
      (node (ref "U7") (pin "17") (pinfunction "B3_17") (pintype "bidirectional"))
    )
    (net (code "74") (name "unconnected-(U7-B4-Pad16)") (class "Default")
      (node (ref "U7") (pin "16") (pinfunction "B4_16") (pintype "bidirectional"))
    )
    (net (code "75") (name "unconnected-(U7-B5-Pad15)") (class "Default")
      (node (ref "U7") (pin "15") (pinfunction "B5_15") (pintype "bidirectional"))
    )
    (net (code "76") (name "unconnected-(U7-B6-Pad14)") (class "Default")
      (node (ref "U7") (pin "14") (pinfunction "B6_14") (pintype "bidirectional"))
    )
    (net (code "77") (name "unconnected-(U7-B7-Pad13)") (class "Default")
      (node (ref "U7") (pin "13") (pinfunction "B7_13") (pintype "bidirectional"))
    )
    (net (code "78") (name "unconnected-(U7-B8-Pad12)") (class "Default")
      (node (ref "U7") (pin "12") (pinfunction "B8_12") (pintype "bidirectional"))
    )
    (net (code "79") (name "unconnected-(U7-GND-Pad11)") (class "Default")
      (node (ref "U7") (pin "11") (pinfunction "GND_11") (pintype "bidirectional"))
    )
    (net (code "80") (name "unconnected-(U7-OE-Pad10)") (class "Default")
      (node (ref "U7") (pin "10") (pinfunction "OE_10") (pintype "bidirectional"))
    )
    (net (code "81") (name "unconnected-(U7-VCCA-Pad2)") (class "Default")
      (node (ref "U7") (pin "2") (pinfunction "VCCA_2") (pintype "bidirectional"))
    )
    (net (code "82") (name "unconnected-(U7-VCCB-Pad19)") (class "Default")
      (node (ref "U7") (pin "19") (pinfunction "VCCB_19") (pintype "bidirectional"))
    )
  )
)
